# logger_power.net
KiCad netlist of a schematic drawn in Altium Designer
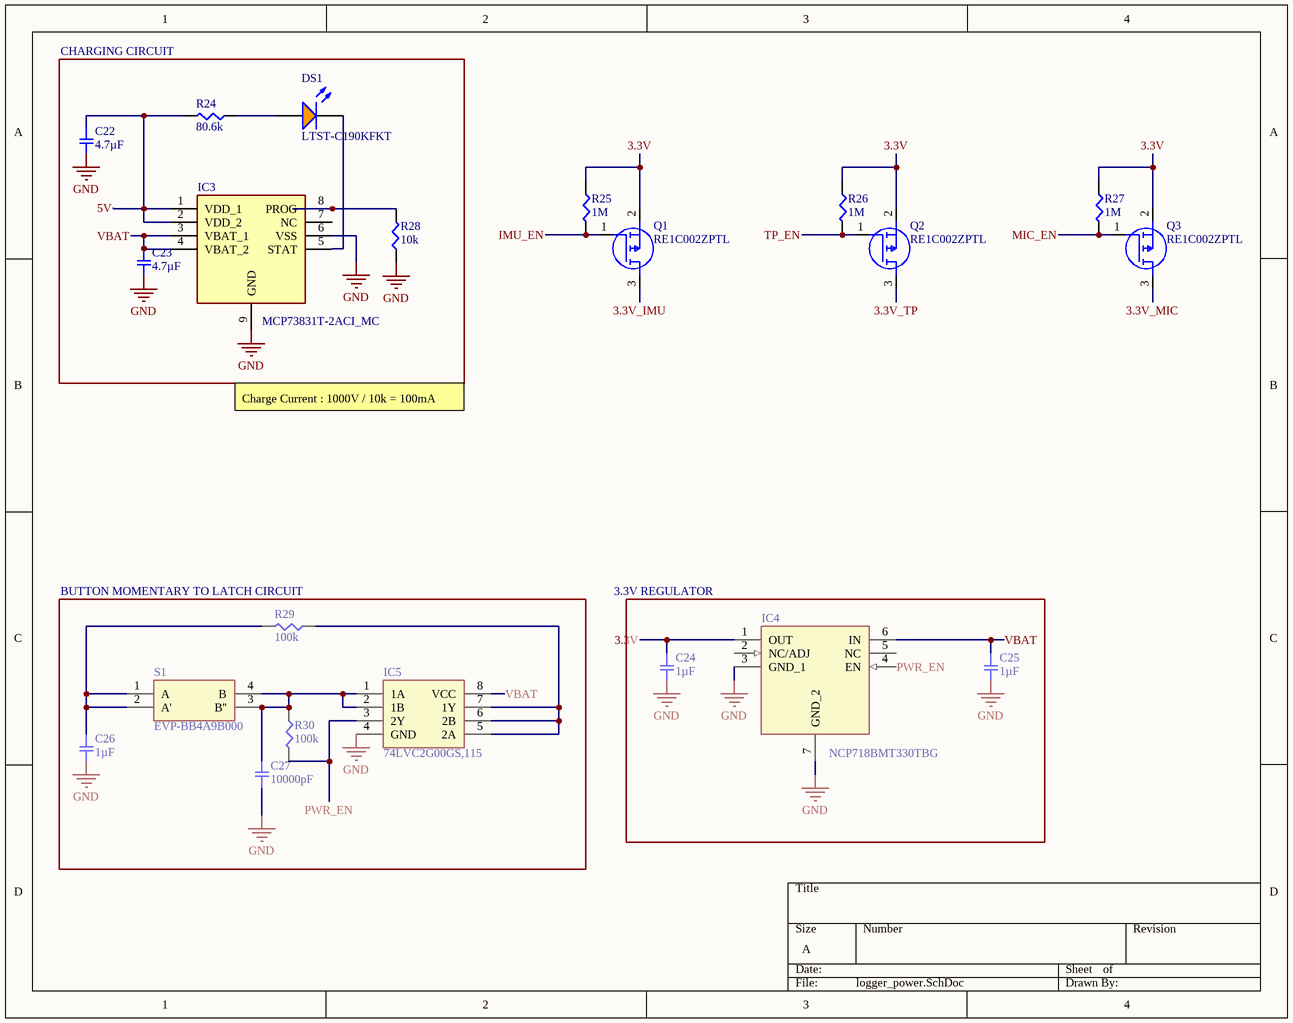
[diagram p0: logger_power.SchDoc]

(export (version "E")
  (design (tool "Eeschema 10.0.6"))
  (components
    (comp (ref "C22")
      (value "4.7µF")
      (footprint "SMD-0402C")
      (description "CAP CER 4.7UF 4V X5R 0402")
      (fields
        (field (name "DIGI-KEY PART NUMBER") "490-13231-1-ND")
        (field (name "PART NUMBER") "GRM153R60G475ME15D")
      )
      (libsource (lib "capacitor_murata_0402") (part "GRM153R60G475ME15D"))
    )
    (comp (ref "C23")
      (value "4.7µF")
      (footprint "SMD-0402C")
      (description "CAP CER 4.7UF 4V X5R 0402")
      (fields
        (field (name "DIGI-KEY PART NUMBER") "490-13231-1-ND")
        (field (name "PART NUMBER") "GRM153R60G475ME15D")
      )
      (libsource (lib "capacitor_murata_0402") (part "GRM153R60G475ME15D"))
    )
    (comp (ref "C24")
      (value "1µF")
      (footprint "SMD-0402C")
      (description "CAP CER 1UF 10V X7S 0402")
      (fields
        (field (name "DIGI-KEY PART NUMBER") "490-13409-1-ND")
        (field (name "PART NUMBER") "GCM155C71A105KE38D")
      )
      (libsource (lib "capacitor_murata_0402") (part "GCM155C71A105KE38D"))
    )
    (comp (ref "C25")
      (value "1µF")
      (footprint "SMD-0402C")
      (description "CAP CER 1UF 10V X7S 0402")
      (fields
        (field (name "DIGI-KEY PART NUMBER") "490-13409-1-ND")
        (field (name "PART NUMBER") "GCM155C71A105KE38D")
      )
      (libsource (lib "capacitor_murata_0402") (part "GCM155C71A105KE38D"))
    )
    (comp (ref "C26")
      (value "1µF")
      (footprint "SMD-0402C")
      (description "CAP CER 1UF 10V X7S 0402")
      (fields
        (field (name "DIGI-KEY PART NUMBER") "490-13409-1-ND")
        (field (name "PART NUMBER") "GCM155C71A105KE38D")
      )
      (libsource (lib "capacitor_murata_0402") (part "GCM155C71A105KE38D"))
    )
    (comp (ref "C27")
      (value "10000pF")
      (footprint "SMD-0402C")
      (description "CAP CER 10000PF 50V X7R 0402")
      (fields
        (field (name "DIGI-KEY PART NUMBER") "490-4762-1-ND")
        (field (name "PART NUMBER") "GCM155R71H103KA55D")
      )
      (libsource (lib "capacitor_murata_0402") (part "GCM155R71H103KA55D"))
    )
    (comp (ref "DS1")
      (value "LTST-C190KFKT")
      (footprint "LTST-C190KFKT_V")
      (description "LED Uni-Color Orange, 75 mW, 30 mA, -35 to 85 degC, 2-Pin SMD, RoHS, Tape and Reel")
      (fields (field (name "TOLERANCE") "1%"))
      (libsource (lib "Altium Content Vault") (part "LED-ORANGE-AK-2"))
    )
    (comp (ref "IC3")
      (value "MCP73831T-2ACI_MC")
      (footprint "SON65P300X300X100-9N-D")
      (description "Integrated Circuit")
      (fields
        (field (name "MANUFACTURER_PART_NUMBER") "MCP73831T-2ACI/MC")
        (field (name "MOUSER PART NUMBER") "579-MCP73831T-2ACIMC")
      )
      (libsource (lib "SamacSys") (part "MCP73831T-2ACI_MC"))
    )
    (comp (ref "IC4")
      (value "NCP718BMT330TBG")
      (footprint "SamacSys:SON65P200X200X80-7N")
      (description "Integrated Circuit")
      (fields
        (field (name "MOUSER PART NUMBER") "863-NCP718BMT330TBG")
        (field (name "RS PART NUMBER") "1861278")
      )
      (libsource (lib "*") (part "NCP718BMT330TBG"))
    )
    (comp (ref "IC5")
      (value "74LVC2G00GS,115")
      (footprint "SamacSys:74AXP2T3407GSX")
      (description "Integrated Circuit")
      (libsource (lib "*") (part "74LVC2G00GS,115"))
    )
    (comp (ref "Q1")
      (value "RE1C002ZPTL")
      (footprint "SamacSys:SOTFL50P160X85-3N")
      (description "MOSFET (P-Channel)")
      (fields
        (field (name "MOUSER PART NUMBER") "755-RE1C002ZPTL")
        (field (name "RS PART NUMBER") "1486960P")
      )
      (libsource (lib "*") (part "RE1C002ZPTL"))
    )
    (comp (ref "Q2")
      (value "RE1C002ZPTL")
      (footprint "SamacSys:SOTFL50P160X85-3N")
      (description "MOSFET (P-Channel)")
      (fields
        (field (name "MOUSER PART NUMBER") "755-RE1C002ZPTL")
        (field (name "RS PART NUMBER") "1486960P")
      )
      (libsource (lib "*") (part "RE1C002ZPTL"))
    )
    (comp (ref "Q3")
      (value "RE1C002ZPTL")
      (footprint "SamacSys:SOTFL50P160X85-3N")
      (description "MOSFET (P-Channel)")
      (fields
        (field (name "MOUSER PART NUMBER") "755-RE1C002ZPTL")
        (field (name "RS PART NUMBER") "1486960P")
      )
      (libsource (lib "*") (part "RE1C002ZPTL"))
    )
    (comp (ref "R24")
      (value "80.6k")
      (footprint "SMD-0402-RES")
      (description "RES SMD 80.6K OHM 1% 1/10W 0402")
      (fields
        (field (name "PART NUMBER") "ERJ-2RKF8062X")
        (field (name "DIGI-KEY PART NUMBER") "P80.6KLCT-ND")
      )
      (libsource (lib "Panasonic_ERJ_0402") (part "ERJ-2RKF8062X"))
    )
    (comp (ref "R25")
      (value "1M")
      (footprint "SMD-0402-RES")
      (description "RES SMD 1M OHM 5% 1/10W 0402")
      (fields (field (name "PART NUMBER") "ERJ-2GEJ105X") (field (name "DIGI-KEY PART NUMBER") "P1.0MJCT-ND"))
      (libsource (lib "Panasonic_ERJ_0402") (part "ERJ-2GEJ105X"))
    )
    (comp (ref "R26")
      (value "1M")
      (footprint "SMD-0402-RES")
      (description "RES SMD 1M OHM 5% 1/10W 0402")
      (fields (field (name "PART NUMBER") "ERJ-2GEJ105X") (field (name "DIGI-KEY PART NUMBER") "P1.0MJCT-ND"))
      (libsource (lib "Panasonic_ERJ_0402") (part "ERJ-2GEJ105X"))
    )
    (comp (ref "R27")
      (value "1M")
      (footprint "SMD-0402-RES")
      (description "RES SMD 1M OHM 5% 1/10W 0402")
      (fields (field (name "PART NUMBER") "ERJ-2GEJ105X") (field (name "DIGI-KEY PART NUMBER") "P1.0MJCT-ND"))
      (libsource (lib "Panasonic_ERJ_0402") (part "ERJ-2GEJ105X"))
    )
    (comp (ref "R28")
      (value "10k")
      (footprint "SMD-0402-RES")
      (description "RES SMD 10K OHM 5% 1/10W 0402")
      (fields (field (name "PART NUMBER") "ERJ-2GEJ103X") (field (name "DIGI-KEY PART NUMBER") "P10KJCT-ND"))
      (libsource (lib "Panasonic_ERJ_0402") (part "ERJ-2GEJ103X"))
    )
    (comp (ref "R29")
      (value "100k")
      (footprint "SMD-0402-RES")
      (description "RES SMD 100K OHM 5% 1/10W 0402")
      (fields (field (name "PART NUMBER") "ERJ-2GEJ104X") (field (name "DIGI-KEY PART NUMBER") "P100KJCT-ND"))
      (libsource (lib "Panasonic_ERJ_0402") (part "ERJ-2GEJ104X"))
    )
    (comp (ref "R30")
      (value "100k")
      (footprint "SMD-0402-RES")
      (description "RES SMD 100K OHM 5% 1/10W 0402")
      (fields (field (name "PART NUMBER") "ERJ-2GEJ104X") (field (name "DIGI-KEY PART NUMBER") "P100KJCT-ND"))
      (libsource (lib "Panasonic_ERJ_0402") (part "ERJ-2GEJ104X"))
    )
    (comp (ref "S1")
      (value "EVP-BB4A9B000")
      (footprint "SamacSys:EVPBB2A9B000")
      (description "Switch")
      (fields (field (name "MOUSER PART NUMBER") "667-EVP-BB4A9B000"))
      (libsource (lib "*") (part "EVP-BB4A9B000"))
    )
  )
  (nets
    (net (code "1") (name "/3.3V") (class "Default")
      (node (ref "C24") (pin "1") (pinfunction "1_1") (pintype "passive"))
      (node (ref "IC4") (pin "1") (pinfunction "OUT_1") (pintype "power_in"))
      (node (ref "Q1") (pin "2") (pinfunction "S_2") (pintype "passive"))
      (node (ref "Q2") (pin "2") (pinfunction "S_2") (pintype "passive"))
      (node (ref "Q3") (pin "2") (pinfunction "S_2") (pintype "passive"))
      (node (ref "R25") (pin "1") (pinfunction "1_1") (pintype "passive"))
      (node (ref "R26") (pin "1") (pinfunction "1_1") (pintype "passive"))
      (node (ref "R27") (pin "1") (pinfunction "1_1") (pintype "passive"))
    )
    (net (code "2") (name "/3.3V_IMU") (class "Default")
      (node (ref "Q1") (pin "3") (pinfunction "D_3") (pintype "passive"))
    )
    (net (code "3") (name "/3.3V_MIC") (class "Default")
      (node (ref "Q3") (pin "3") (pinfunction "D_3") (pintype "passive"))
    )
    (net (code "4") (name "/3.3V_TP") (class "Default")
      (node (ref "Q2") (pin "3") (pinfunction "D_3") (pintype "passive"))
    )
    (net (code "5") (name "/5V") (class "Default")
      (node (ref "C22") (pin "1") (pinfunction "1_1") (pintype "passive"))
      (node (ref "IC3") (pin "1") (pinfunction "VDD_1_1") (pintype "passive"))
      (node (ref "IC3") (pin "2") (pinfunction "VDD_2_2") (pintype "passive"))
      (node (ref "R24") (pin "2") (pinfunction "2_2") (pintype "passive"))
    )
    (net (code "6") (name "/IMU_EN") (class "Default")
      (node (ref "Q1") (pin "1") (pinfunction "G_1") (pintype "passive"))
      (node (ref "R25") (pin "2") (pinfunction "2_2") (pintype "passive"))
    )
    (net (code "7") (name "/MIC_EN") (class "Default")
      (node (ref "Q3") (pin "1") (pinfunction "G_1") (pintype "passive"))
      (node (ref "R27") (pin "2") (pinfunction "2_2") (pintype "passive"))
    )
    (net (code "8") (name "/PWR_EN") (class "Default")
      (node (ref "IC4") (pin "4") (pinfunction "EN_4") (pintype "input"))
      (node (ref "IC5") (pin "3") (pinfunction "2Y_3") (pintype "passive"))
      (node (ref "R30") (pin "2") (pinfunction "2_2") (pintype "passive"))
    )
    (net (code "9") (name "/TP_EN") (class "Default")
      (node (ref "Q2") (pin "1") (pinfunction "G_1") (pintype "passive"))
      (node (ref "R26") (pin "2") (pinfunction "2_2") (pintype "passive"))
    )
    (net (code "10") (name "/VBAT") (class "Default")
      (node (ref "C23") (pin "1") (pinfunction "1_1") (pintype "passive"))
      (node (ref "C25") (pin "1") (pinfunction "1_1") (pintype "passive"))
      (node (ref "IC3") (pin "3") (pinfunction "VBAT_1_3") (pintype "passive"))
      (node (ref "IC3") (pin "4") (pinfunction "VBAT_2_4") (pintype "passive"))
      (node (ref "IC4") (pin "6") (pinfunction "IN_6") (pintype "power_in"))
      (node (ref "IC5") (pin "8") (pinfunction "VCC_8") (pintype "passive"))
    )
    (net (code "11") (name "GND") (class "Default")
      (node (ref "C22") (pin "2") (pinfunction "2_2") (pintype "passive"))
      (node (ref "C23") (pin "2") (pinfunction "2_2") (pintype "passive"))
      (node (ref "C24") (pin "2") (pinfunction "2_2") (pintype "passive"))
      (node (ref "C25") (pin "2") (pinfunction "2_2") (pintype "passive"))
      (node (ref "C26") (pin "2") (pinfunction "2_2") (pintype "passive"))
      (node (ref "C27") (pin "1") (pinfunction "1_1") (pintype "passive"))
      (node (ref "IC3") (pin "6") (pinfunction "VSS_6") (pintype "passive"))
      (node (ref "IC3") (pin "9") (pinfunction "GND_9") (pintype "passive"))
      (node (ref "IC4") (pin "3") (pinfunction "GND_1_3") (pintype "power_in"))
      (node (ref "IC4") (pin "7") (pinfunction "GND_2_7") (pintype "power_in"))
      (node (ref "IC5") (pin "4") (pinfunction "GND_4") (pintype "passive"))
      (node (ref "R28") (pin "1") (pinfunction "1_1") (pintype "passive"))
    )
    (net (code "12") (name "Net-(DS1-A)") (class "Default")
      (node (ref "DS1") (pin "1") (pinfunction "A_1") (pintype "passive"))
      (node (ref "R24") (pin "1") (pinfunction "1_1") (pintype "passive"))
    )
    (net (code "13") (name "Net-(DS1-K)") (class "Default")
      (node (ref "DS1") (pin "2") (pinfunction "K_2") (pintype "passive"))
      (node (ref "IC3") (pin "5") (pinfunction "STAT_5") (pintype "passive"))
    )
    (net (code "14") (name "Net-(IC3-PROG)") (class "Default")
      (node (ref "IC3") (pin "8") (pinfunction "PROG_8") (pintype "passive"))
      (node (ref "R28") (pin "2") (pinfunction "2_2") (pintype "passive"))
    )
    (net (code "15") (name "Net-(IC5-1A)") (class "Default")
      (node (ref "C27") (pin "2") (pinfunction "2_2") (pintype "passive"))
      (node (ref "IC5") (pin "1") (pinfunction "1A_1") (pintype "passive"))
      (node (ref "IC5") (pin "2") (pinfunction "1B_2") (pintype "passive"))
      (node (ref "R30") (pin "1") (pinfunction "1_1") (pintype "passive"))
      (node (ref "S1") (pin "3") (pinfunction "B''_3") (pintype "passive"))
      (node (ref "S1") (pin "4") (pinfunction "B_4") (pintype "passive"))
    )
    (net (code "16") (name "Net-(IC5-1Y)") (class "Default")
      (node (ref "IC5") (pin "5") (pinfunction "2A_5") (pintype "passive"))
      (node (ref "IC5") (pin "6") (pinfunction "2B_6") (pintype "passive"))
      (node (ref "IC5") (pin "7") (pinfunction "1Y_7") (pintype "passive"))
      (node (ref "R29") (pin "1") (pinfunction "1_1") (pintype "passive"))
    )
    (net (code "17") (name "Net-(S1-A')") (class "Default")
      (node (ref "C26") (pin "1") (pinfunction "1_1") (pintype "passive"))
      (node (ref "R29") (pin "2") (pinfunction "2_2") (pintype "passive"))
      (node (ref "S1") (pin "1") (pinfunction "A_1") (pintype "passive"))
      (node (ref "S1") (pin "2") (pinfunction "A'_2") (pintype "passive"))
    )
    (net (code "18") (name "unconnected-(IC3-NC-Pad7)") (class "Default")
      (node (ref "IC3") (pin "7") (pinfunction "NC_7") (pintype "passive"))
    )
    (net (code "19") (name "unconnected-(IC4-NC-Pad5)") (class "Default")
      (node (ref "IC4") (pin "5") (pinfunction "NC_5") (pintype "passive"))
    )
    (net (code "20") (name "unconnected-(IC4-NC{slash}ADJ-Pad2)") (class "Default")
      (node (ref "IC4") (pin "2") (pinfunction "NC/ADJ_2") (pintype "input"))
    )
  )
)
